# 201944AEP4P01.net
KiCad netlist of a schematic drawn in Altium Designer
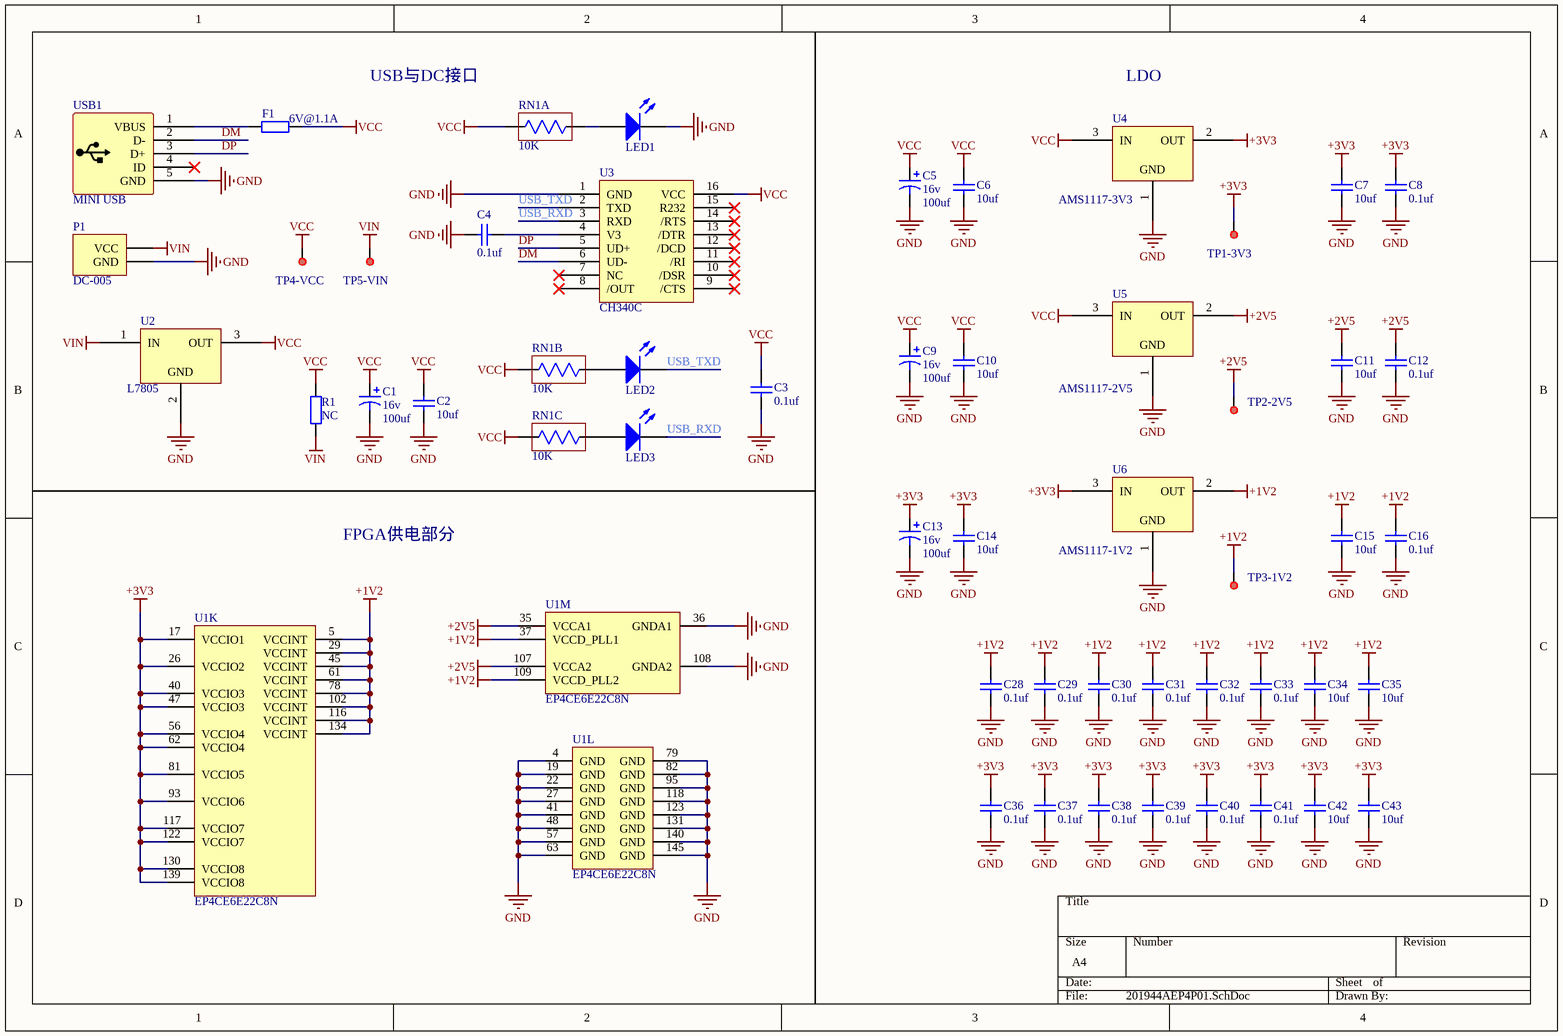
[diagram p0: 201944AEP4P01.SchDoc]

(export (version "E")
  (design (tool "Eeschema 10.0.6"))
  (components
    (comp (ref "C1")
      (value "100uf")
      (footprint "C5X11")
      (fields (field (name "VOLTAGE") "16v") (field (name "Comment") "Cap2"))
      (libsource (lib "carrot_lib") (part "Cap2"))
    )
    (comp (ref "C2")
      (value "10uf")
      (footprint "C1206")
      (fields (field (name "Comment") "Cap"))
      (libsource (lib "carrot_lib") (part "Cap"))
    )
    (comp (ref "C3")
      (value "0.1uf")
      (footprint "C0805")
      (fields (field (name "Comment") "Cap"))
      (libsource (lib "carrot_lib") (part "Cap"))
    )
    (comp (ref "C4")
      (value "0.1uf")
      (footprint "C0805")
      (fields (field (name "Comment") "Cap"))
      (libsource (lib "carrot_lib") (part "Cap"))
    )
    (comp (ref "C5")
      (value "100uf")
      (footprint "C5X11")
      (fields (field (name "VOLTAGE") "16v") (field (name "Comment") "Cap2"))
      (libsource (lib "carrot_lib") (part "Cap2"))
    )
    (comp (ref "C6")
      (value "10uf")
      (footprint "C1206")
      (fields (field (name "Comment") "Cap"))
      (libsource (lib "carrot_lib") (part "Cap"))
    )
    (comp (ref "C7")
      (value "10uf")
      (footprint "C0805")
      (fields (field (name "Comment") "Cap"))
      (libsource (lib "carrot_lib") (part "Cap"))
    )
    (comp (ref "C8")
      (value "0.1uf")
      (footprint "C0805")
      (fields (field (name "Comment") "Cap"))
      (libsource (lib "carrot_lib") (part "Cap"))
    )
    (comp (ref "C9")
      (value "100uf")
      (footprint "C5X11")
      (fields (field (name "VOLTAGE") "16v") (field (name "Comment") "Cap2"))
      (libsource (lib "carrot_lib") (part "Cap2"))
    )
    (comp (ref "C10")
      (value "10uf")
      (footprint "C1206")
      (fields (field (name "Comment") "Cap"))
      (libsource (lib "carrot_lib") (part "Cap"))
    )
    (comp (ref "C11")
      (value "10uf")
      (footprint "C0805")
      (fields (field (name "Comment") "Cap"))
      (libsource (lib "carrot_lib") (part "Cap"))
    )
    (comp (ref "C12")
      (value "0.1uf")
      (footprint "C0805")
      (fields (field (name "Comment") "Cap"))
      (libsource (lib "carrot_lib") (part "Cap"))
    )
    (comp (ref "C13")
      (value "100uf")
      (footprint "C5X11")
      (fields (field (name "VOLTAGE") "16v") (field (name "Comment") "Cap2"))
      (libsource (lib "carrot_lib") (part "Cap2"))
    )
    (comp (ref "C14")
      (value "10uf")
      (footprint "C1206")
      (fields (field (name "Comment") "Cap"))
      (libsource (lib "carrot_lib") (part "Cap"))
    )
    (comp (ref "C15")
      (value "10uf")
      (footprint "C0805")
      (fields (field (name "Comment") "Cap"))
      (libsource (lib "carrot_lib") (part "Cap"))
    )
    (comp (ref "C16")
      (value "0.1uf")
      (footprint "C0805")
      (fields (field (name "Comment") "Cap"))
      (libsource (lib "carrot_lib") (part "Cap"))
    )
    (comp (ref "C28")
      (value "0.1uf")
      (footprint "C0805")
      (fields (field (name "Comment") "Cap"))
      (libsource (lib "carrot_lib") (part "Cap"))
    )
    (comp (ref "C29")
      (value "0.1uf")
      (footprint "C0805")
      (fields (field (name "Comment") "Cap"))
      (libsource (lib "carrot_lib") (part "Cap"))
    )
    (comp (ref "C30")
      (value "0.1uf")
      (footprint "C0805")
      (fields (field (name "Comment") "Cap"))
      (libsource (lib "carrot_lib") (part "Cap"))
    )
    (comp (ref "C31")
      (value "0.1uf")
      (footprint "C0805")
      (fields (field (name "Comment") "Cap"))
      (libsource (lib "carrot_lib") (part "Cap"))
    )
    (comp (ref "C32")
      (value "0.1uf")
      (footprint "C0805")
      (fields (field (name "Comment") "Cap"))
      (libsource (lib "carrot_lib") (part "Cap"))
    )
    (comp (ref "C33")
      (value "0.1uf")
      (footprint "C0805")
      (fields (field (name "Comment") "Cap"))
      (libsource (lib "carrot_lib") (part "Cap"))
    )
    (comp (ref "C34")
      (value "10uf")
      (footprint "C0805")
      (fields (field (name "Comment") "Cap"))
      (libsource (lib "carrot_lib") (part "Cap"))
    )
    (comp (ref "C35")
      (value "10uf")
      (footprint "C0805")
      (fields (field (name "Comment") "Cap"))
      (libsource (lib "carrot_lib") (part "Cap"))
    )
    (comp (ref "C36")
      (value "0.1uf")
      (footprint "C0805")
      (fields (field (name "Comment") "Cap"))
      (libsource (lib "carrot_lib") (part "Cap"))
    )
    (comp (ref "C37")
      (value "0.1uf")
      (footprint "C0805")
      (fields (field (name "Comment") "Cap"))
      (libsource (lib "carrot_lib") (part "Cap"))
    )
    (comp (ref "C38")
      (value "0.1uf")
      (footprint "C0805")
      (fields (field (name "Comment") "Cap"))
      (libsource (lib "carrot_lib") (part "Cap"))
    )
    (comp (ref "C39")
      (value "0.1uf")
      (footprint "C0805")
      (fields (field (name "Comment") "Cap"))
      (libsource (lib "carrot_lib") (part "Cap"))
    )
    (comp (ref "C40")
      (value "0.1uf")
      (footprint "C0805")
      (fields (field (name "Comment") "Cap"))
      (libsource (lib "carrot_lib") (part "Cap"))
    )
    (comp (ref "C41")
      (value "0.1uf")
      (footprint "C0805")
      (fields (field (name "Comment") "Cap"))
      (libsource (lib "carrot_lib") (part "Cap"))
    )
    (comp (ref "C42")
      (value "10uf")
      (footprint "C0805")
      (fields (field (name "Comment") "Cap"))
      (libsource (lib "carrot_lib") (part "Cap"))
    )
    (comp (ref "C43")
      (value "10uf")
      (footprint "C0805")
      (fields (field (name "Comment") "Cap"))
      (libsource (lib "carrot_lib") (part "Cap"))
    )
    (comp (ref "F1")
      (value "6V@1.1A")
      (footprint "R1206")
      (fields (field (name "Comment") "Res"))
      (libsource (lib "") (part "Res_1"))
    )
    (comp (ref "LED1") (value "LED") (footprint "LED1206") (libsource (lib "carrot_lib") (part "LED")))
    (comp (ref "LED2") (value "LED") (footprint "LED1206") (libsource (lib "carrot_lib") (part "LED")))
    (comp (ref "LED3") (value "LED") (footprint "LED1206") (libsource (lib "carrot_lib") (part "LED")))
    (comp (ref "P1") (value "DC-005") (footprint "DC-005") (libsource (lib "carrot_lib") (part "DC-005")))
    (comp (ref "R1")
      (value "NC")
      (footprint "R0805")
      (fields (field (name "Comment") "Res"))
      (libsource (lib "carrot_lib") (part "Res"))
    )
    (comp (ref "RN1")
      (value "10K")
      (footprint "RA0603")
      (description "贴片排阻")
      (fields (field (name "Comment") "Res Array"))
      (libsource (lib "carrot_lib") (part "Res Array 2"))
    )
    (comp (ref "TP1-3V3")
      (value "TestPoint")
      (footprint "TestPoint-R20")
      (description "测试点")
      (libsource (lib "carrot_lib") (part "TestPoint"))
    )
    (comp (ref "TP2-2V5")
      (value "TestPoint")
      (footprint "TestPoint-R20")
      (description "测试点")
      (libsource (lib "carrot_lib") (part "TestPoint"))
    )
    (comp (ref "TP3-1V2")
      (value "TestPoint")
      (footprint "TestPoint-R20")
      (description "测试点")
      (libsource (lib "carrot_lib") (part "TestPoint"))
    )
    (comp (ref "TP4-VCC")
      (value "TestPoint")
      (footprint "TestPoint-R20")
      (description "测试点")
      (libsource (lib "carrot_lib") (part "TestPoint"))
    )
    (comp (ref "TP5-VIN")
      (value "TestPoint")
      (footprint "TestPoint-R20")
      (description "测试点")
      (libsource (lib "carrot_lib") (part "TestPoint"))
    )
    (comp (ref "U1")
      (value "EP4CE6E22C8N")
      (footprint "EP4CE6E22C8N-EQFP144+")
      (fields (field (name "MANUFACTURER") "Altera"))
      (libsource (lib "carrot_lib") (part "EP4CE6E22C8N"))
    )
    (comp (ref "U2") (value "L7805") (footprint "L7805-TO252") (libsource (lib "carrot_lib") (part "L7805")))
    (comp (ref "U3")
      (value "CH340C")
      (footprint "CH340C-SOP16")
      (description "USB 转串口芯片")
      (libsource (lib "carrot_lib") (part "CH340C"))
    )
    (comp (ref "U4")
      (value "AMS1117-3V3")
      (footprint "AMS1117-SOT223")
      (libsource (lib "carrot_lib") (part "AMS1117"))
    )
    (comp (ref "U5")
      (value "AMS1117-2V5")
      (footprint "AMS1117-SOT223")
      (libsource (lib "carrot_lib") (part "AMS1117"))
    )
    (comp (ref "U6")
      (value "AMS1117-1V2")
      (footprint "AMS1117-SOT223")
      (libsource (lib "carrot_lib") (part "AMS1117"))
    )
    (comp (ref "USB1")
      (value "MINI USB")
      (footprint "USB-Mini-SMT")
      (libsource (lib "carrot_lib") (part "USB"))
    )
  )
  (nets
    (net (code "1") (name "+1V2") (class "Default")
      (node (ref "C15") (pin "2") (pinfunction "2_2") (pintype "passive"))
      (node (ref "C16") (pin "2") (pinfunction "2_2") (pintype "passive"))
      (node (ref "C28") (pin "2") (pinfunction "2_2") (pintype "passive"))
      (node (ref "C29") (pin "2") (pinfunction "2_2") (pintype "passive"))
      (node (ref "C30") (pin "2") (pinfunction "2_2") (pintype "passive"))
      (node (ref "C31") (pin "2") (pinfunction "2_2") (pintype "passive"))
      (node (ref "C32") (pin "2") (pinfunction "2_2") (pintype "passive"))
      (node (ref "C33") (pin "2") (pinfunction "2_2") (pintype "passive"))
      (node (ref "C34") (pin "2") (pinfunction "2_2") (pintype "passive"))
      (node (ref "C35") (pin "2") (pinfunction "2_2") (pintype "passive"))
      (node (ref "TP3-1V2") (pin "1") (pinfunction "1_1") (pintype "passive"))
      (node (ref "U1") (pin "102") (pinfunction "VCCINT_102") (pintype "power_in"))
      (node (ref "U1") (pin "109") (pinfunction "VCCD_PLL2_109") (pintype "power_in"))
      (node (ref "U1") (pin "116") (pinfunction "VCCINT_116") (pintype "power_in"))
      (node (ref "U1") (pin "134") (pinfunction "VCCINT_134") (pintype "power_in"))
      (node (ref "U1") (pin "29") (pinfunction "VCCINT_29") (pintype "power_in"))
      (node (ref "U1") (pin "37") (pinfunction "VCCD_PLL1_37") (pintype "power_in"))
      (node (ref "U1") (pin "45") (pinfunction "VCCINT_45") (pintype "power_in"))
      (node (ref "U1") (pin "5") (pinfunction "VCCINT_5") (pintype "power_in"))
      (node (ref "U1") (pin "61") (pinfunction "VCCINT_61") (pintype "power_in"))
      (node (ref "U1") (pin "78") (pinfunction "VCCINT_78") (pintype "power_in"))
      (node (ref "U6") (pin "2") (pinfunction "OUT_2") (pintype "passive"))
    )
    (net (code "2") (name "+2V5") (class "Default")
      (node (ref "C11") (pin "2") (pinfunction "2_2") (pintype "passive"))
      (node (ref "C12") (pin "2") (pinfunction "2_2") (pintype "passive"))
      (node (ref "TP2-2V5") (pin "1") (pinfunction "1_1") (pintype "passive"))
      (node (ref "U1") (pin "107") (pinfunction "VCCA2_107") (pintype "power_in"))
      (node (ref "U1") (pin "35") (pinfunction "VCCA1_35") (pintype "power_in"))
      (node (ref "U5") (pin "2") (pinfunction "OUT_2") (pintype "passive"))
    )
    (net (code "3") (name "+3V3") (class "Default")
      (node (ref "C13") (pin "1") (pinfunction "1_1") (pintype "passive"))
      (node (ref "C14") (pin "2") (pinfunction "2_2") (pintype "passive"))
      (node (ref "C36") (pin "2") (pinfunction "2_2") (pintype "passive"))
      (node (ref "C37") (pin "2") (pinfunction "2_2") (pintype "passive"))
      (node (ref "C38") (pin "2") (pinfunction "2_2") (pintype "passive"))
      (node (ref "C39") (pin "2") (pinfunction "2_2") (pintype "passive"))
      (node (ref "C40") (pin "2") (pinfunction "2_2") (pintype "passive"))
      (node (ref "C41") (pin "2") (pinfunction "2_2") (pintype "passive"))
      (node (ref "C42") (pin "2") (pinfunction "2_2") (pintype "passive"))
      (node (ref "C43") (pin "2") (pinfunction "2_2") (pintype "passive"))
      (node (ref "C7") (pin "2") (pinfunction "2_2") (pintype "passive"))
      (node (ref "C8") (pin "2") (pinfunction "2_2") (pintype "passive"))
      (node (ref "TP1-3V3") (pin "1") (pinfunction "1_1") (pintype "passive"))
      (node (ref "U1") (pin "117") (pinfunction "VCCIO7_117") (pintype "power_in"))
      (node (ref "U1") (pin "122") (pinfunction "VCCIO7_122") (pintype "power_in"))
      (node (ref "U1") (pin "130") (pinfunction "VCCIO8_130") (pintype "power_in"))
      (node (ref "U1") (pin "139") (pinfunction "VCCIO8_139") (pintype "power_in"))
      (node (ref "U1") (pin "17") (pinfunction "VCCIO1_17") (pintype "power_in"))
      (node (ref "U1") (pin "26") (pinfunction "VCCIO2_26") (pintype "power_in"))
      (node (ref "U1") (pin "40") (pinfunction "VCCIO3_40") (pintype "power_in"))
      (node (ref "U1") (pin "47") (pinfunction "VCCIO3_47") (pintype "power_in"))
      (node (ref "U1") (pin "56") (pinfunction "VCCIO4_56") (pintype "power_in"))
      (node (ref "U1") (pin "62") (pinfunction "VCCIO4_62") (pintype "power_in"))
      (node (ref "U1") (pin "81") (pinfunction "VCCIO5_81") (pintype "power_in"))
      (node (ref "U1") (pin "93") (pinfunction "VCCIO6_93") (pintype "power_in"))
      (node (ref "U4") (pin "2") (pinfunction "OUT_2") (pintype "passive"))
      (node (ref "U6") (pin "3") (pinfunction "IN_3") (pintype "passive"))
    )
    (net (code "4") (name "/DM") (class "Default")
      (node (ref "U3") (pin "6") (pinfunction "UD-_6") (pintype "passive"))
      (node (ref "USB1") (pin "2") (pinfunction "D-_2") (pintype "passive"))
    )
    (net (code "5") (name "/DP") (class "Default")
      (node (ref "U3") (pin "5") (pinfunction "UD+_5") (pintype "passive"))
      (node (ref "USB1") (pin "3") (pinfunction "D+_3") (pintype "passive"))
    )
    (net (code "6") (name "/USB_RXD") (class "Default")
      (node (ref "LED3") (pin "2") (pinfunction "K_2") (pintype "passive"))
      (node (ref "U3") (pin "3") (pinfunction "RXD_3") (pintype "passive"))
    )
    (net (code "7") (name "/USB_TXD") (class "Default")
      (node (ref "LED2") (pin "2") (pinfunction "K_2") (pintype "passive"))
      (node (ref "U3") (pin "2") (pinfunction "TXD_2") (pintype "passive"))
    )
    (net (code "8") (name "GND") (class "Default")
      (node (ref "C1") (pin "2") (pinfunction "2_2") (pintype "passive"))
      (node (ref "C10") (pin "1") (pinfunction "1_1") (pintype "passive"))
      (node (ref "C11") (pin "1") (pinfunction "1_1") (pintype "passive"))
      (node (ref "C12") (pin "1") (pinfunction "1_1") (pintype "passive"))
      (node (ref "C13") (pin "2") (pinfunction "2_2") (pintype "passive"))
      (node (ref "C14") (pin "1") (pinfunction "1_1") (pintype "passive"))
      (node (ref "C15") (pin "1") (pinfunction "1_1") (pintype "passive"))
      (node (ref "C16") (pin "1") (pinfunction "1_1") (pintype "passive"))
      (node (ref "C2") (pin "1") (pinfunction "1_1") (pintype "passive"))
      (node (ref "C28") (pin "1") (pinfunction "1_1") (pintype "passive"))
      (node (ref "C29") (pin "1") (pinfunction "1_1") (pintype "passive"))
      (node (ref "C3") (pin "2") (pinfunction "2_2") (pintype "passive"))
      (node (ref "C30") (pin "1") (pinfunction "1_1") (pintype "passive"))
      (node (ref "C31") (pin "1") (pinfunction "1_1") (pintype "passive"))
      (node (ref "C32") (pin "1") (pinfunction "1_1") (pintype "passive"))
      (node (ref "C33") (pin "1") (pinfunction "1_1") (pintype "passive"))
      (node (ref "C34") (pin "1") (pinfunction "1_1") (pintype "passive"))
      (node (ref "C35") (pin "1") (pinfunction "1_1") (pintype "passive"))
      (node (ref "C36") (pin "1") (pinfunction "1_1") (pintype "passive"))
      (node (ref "C37") (pin "1") (pinfunction "1_1") (pintype "passive"))
      (node (ref "C38") (pin "1") (pinfunction "1_1") (pintype "passive"))
      (node (ref "C39") (pin "1") (pinfunction "1_1") (pintype "passive"))
      (node (ref "C4") (pin "2") (pinfunction "2_2") (pintype "passive"))
      (node (ref "C40") (pin "1") (pinfunction "1_1") (pintype "passive"))
      (node (ref "C41") (pin "1") (pinfunction "1_1") (pintype "passive"))
      (node (ref "C42") (pin "1") (pinfunction "1_1") (pintype "passive"))
      (node (ref "C43") (pin "1") (pinfunction "1_1") (pintype "passive"))
      (node (ref "C5") (pin "2") (pinfunction "2_2") (pintype "passive"))
      (node (ref "C6") (pin "1") (pinfunction "1_1") (pintype "passive"))
      (node (ref "C7") (pin "1") (pinfunction "1_1") (pintype "passive"))
      (node (ref "C8") (pin "1") (pinfunction "1_1") (pintype "passive"))
      (node (ref "C9") (pin "2") (pinfunction "2_2") (pintype "passive"))
      (node (ref "LED1") (pin "2") (pinfunction "K_2") (pintype "passive"))
      (node (ref "P1") (pin "2") (pinfunction "GND_2") (pintype "passive"))
      (node (ref "U1") (pin "108") (pinfunction "GNDA2_108") (pintype "power_in"))
      (node (ref "U1") (pin "118") (pinfunction "GND_118") (pintype "power_in"))
      (node (ref "U1") (pin "123") (pinfunction "GND_123") (pintype "power_in"))
      (node (ref "U1") (pin "131") (pinfunction "GND_131") (pintype "power_in"))
      (node (ref "U1") (pin "140") (pinfunction "GND_140") (pintype "power_in"))
      (node (ref "U1") (pin "145") (pinfunction "GND_145") (pintype "power_in"))
      (node (ref "U1") (pin "19") (pinfunction "GND_19") (pintype "power_in"))
      (node (ref "U1") (pin "22") (pinfunction "GND_22") (pintype "power_in"))
      (node (ref "U1") (pin "27") (pinfunction "GND_27") (pintype "power_in"))
      (node (ref "U1") (pin "36") (pinfunction "GNDA1_36") (pintype "power_in"))
      (node (ref "U1") (pin "4") (pinfunction "GND_4") (pintype "power_in"))
      (node (ref "U1") (pin "41") (pinfunction "GND_41") (pintype "power_in"))
      (node (ref "U1") (pin "48") (pinfunction "GND_48") (pintype "power_in"))
      (node (ref "U1") (pin "57") (pinfunction "GND_57") (pintype "power_in"))
      (node (ref "U1") (pin "63") (pinfunction "GND_63") (pintype "power_in"))
      (node (ref "U1") (pin "79") (pinfunction "GND_79") (pintype "power_in"))
      (node (ref "U1") (pin "82") (pinfunction "GND_82") (pintype "power_in"))
      (node (ref "U1") (pin "95") (pinfunction "GND_95") (pintype "power_in"))
      (node (ref "U2") (pin "2") (pinfunction "GND_2") (pintype "passive"))
      (node (ref "U3") (pin "1") (pinfunction "GND_1") (pintype "passive"))
      (node (ref "U4") (pin "1") (pinfunction "GND_1") (pintype "passive"))
      (node (ref "U5") (pin "1") (pinfunction "GND_1") (pintype "passive"))
      (node (ref "U6") (pin "1") (pinfunction "GND_1") (pintype "passive"))
      (node (ref "USB1") (pin "5") (pinfunction "GND_5") (pintype "passive"))
    )
    (net (code "9") (name "Net-(LED1-A)") (class "Default")
      (node (ref "LED1") (pin "1") (pinfunction "A_1") (pintype "passive"))
      (node (ref "RN1") (pin "8") (pinfunction "8_8") (pintype "passive"))
    )
    (net (code "10") (name "Net-(LED2-A)") (class "Default")
      (node (ref "LED2") (pin "1") (pinfunction "A_1") (pintype "passive"))
      (node (ref "RN1") (pin "7") (pinfunction "7_7") (pintype "passive"))
    )
    (net (code "11") (name "Net-(LED3-A)") (class "Default")
      (node (ref "LED3") (pin "1") (pinfunction "A_1") (pintype "passive"))
      (node (ref "RN1") (pin "6") (pinfunction "6_6") (pintype "passive"))
    )
    (net (code "12") (name "Net-(U3-V3)") (class "Default")
      (node (ref "C4") (pin "1") (pinfunction "1_1") (pintype "passive"))
      (node (ref "U3") (pin "4") (pinfunction "V3_4") (pintype "passive"))
    )
    (net (code "13") (name "Net-(USB1-VBUS)") (class "Default")
      (node (ref "F1") (pin "1") (pinfunction "1_1") (pintype "passive"))
      (node (ref "USB1") (pin "1") (pinfunction "VBUS_1") (pintype "passive"))
    )
    (net (code "14") (name "VCC") (class "Default")
      (node (ref "C1") (pin "1") (pinfunction "1_1") (pintype "passive"))
      (node (ref "C10") (pin "2") (pinfunction "2_2") (pintype "passive"))
      (node (ref "C2") (pin "2") (pinfunction "2_2") (pintype "passive"))
      (node (ref "C3") (pin "1") (pinfunction "1_1") (pintype "passive"))
      (node (ref "C5") (pin "1") (pinfunction "1_1") (pintype "passive"))
      (node (ref "C6") (pin "2") (pinfunction "2_2") (pintype "passive"))
      (node (ref "C9") (pin "1") (pinfunction "1_1") (pintype "passive"))
      (node (ref "F1") (pin "2") (pinfunction "2_2") (pintype "passive"))
      (node (ref "R1") (pin "2") (pinfunction "2_2") (pintype "passive"))
      (node (ref "RN1") (pin "1") (pinfunction "1_1") (pintype "passive"))
      (node (ref "RN1") (pin "2") (pinfunction "2_2") (pintype "passive"))
      (node (ref "RN1") (pin "3") (pinfunction "3_3") (pintype "passive"))
      (node (ref "TP4-VCC") (pin "1") (pinfunction "1_1") (pintype "passive"))
      (node (ref "U2") (pin "3") (pinfunction "OUT_3") (pintype "passive"))
      (node (ref "U3") (pin "16") (pinfunction "VCC_16") (pintype "passive"))
      (node (ref "U4") (pin "3") (pinfunction "IN_3") (pintype "passive"))
      (node (ref "U5") (pin "3") (pinfunction "IN_3") (pintype "passive"))
    )
    (net (code "15") (name "VIN") (class "Default")
      (node (ref "P1") (pin "1") (pinfunction "VCC_1") (pintype "passive"))
      (node (ref "R1") (pin "1") (pinfunction "1_1") (pintype "passive"))
      (node (ref "TP5-VIN") (pin "1") (pinfunction "1_1") (pintype "passive"))
      (node (ref "U2") (pin "1") (pinfunction "IN_1") (pintype "passive"))
    )
    (net (code "16") (name "unconnected-(U3-NC-Pad7)") (class "Default")
      (node (ref "U3") (pin "7") (pinfunction "NC_7") (pintype "passive+no_connect"))
    )
    (net (code "17") (name "unconnected-(U3-R232-Pad15)") (class "Default")
      (node (ref "U3") (pin "15") (pinfunction "R232_15") (pintype "passive+no_connect"))
    )
    (net (code "18") (name "unconnected-(U3-{slash}CTS-Pad9)") (class "Default")
      (node (ref "U3") (pin "9") (pinfunction "/CTS_9") (pintype "passive+no_connect"))
    )
    (net (code "19") (name "unconnected-(U3-{slash}DCD-Pad12)") (class "Default")
      (node (ref "U3") (pin "12") (pinfunction "/DCD_12") (pintype "passive+no_connect"))
    )
    (net (code "20") (name "unconnected-(U3-{slash}DSR-Pad10)") (class "Default")
      (node (ref "U3") (pin "10") (pinfunction "/DSR_10") (pintype "passive+no_connect"))
    )
    (net (code "21") (name "unconnected-(U3-{slash}DTR-Pad13)") (class "Default")
      (node (ref "U3") (pin "13") (pinfunction "/DTR_13") (pintype "passive+no_connect"))
    )
    (net (code "22") (name "unconnected-(U3-{slash}OUT-Pad8)") (class "Default")
      (node (ref "U3") (pin "8") (pinfunction "/OUT_8") (pintype "passive+no_connect"))
    )
    (net (code "23") (name "unconnected-(U3-{slash}RI-Pad11)") (class "Default")
      (node (ref "U3") (pin "11") (pinfunction "/RI_11") (pintype "passive+no_connect"))
    )
    (net (code "24") (name "unconnected-(U3-{slash}RTS-Pad14)") (class "Default")
      (node (ref "U3") (pin "14") (pinfunction "/RTS_14") (pintype "passive+no_connect"))
    )
    (net (code "25") (name "unconnected-(USB1-ID-Pad4)") (class "Default")
      (node (ref "USB1") (pin "4") (pinfunction "ID_4") (pintype "passive+no_connect"))
    )
  )
)
